# REV_SPARC_CNC_with_battery.net
KiCad netlist of a schematic drawn in EAGLE
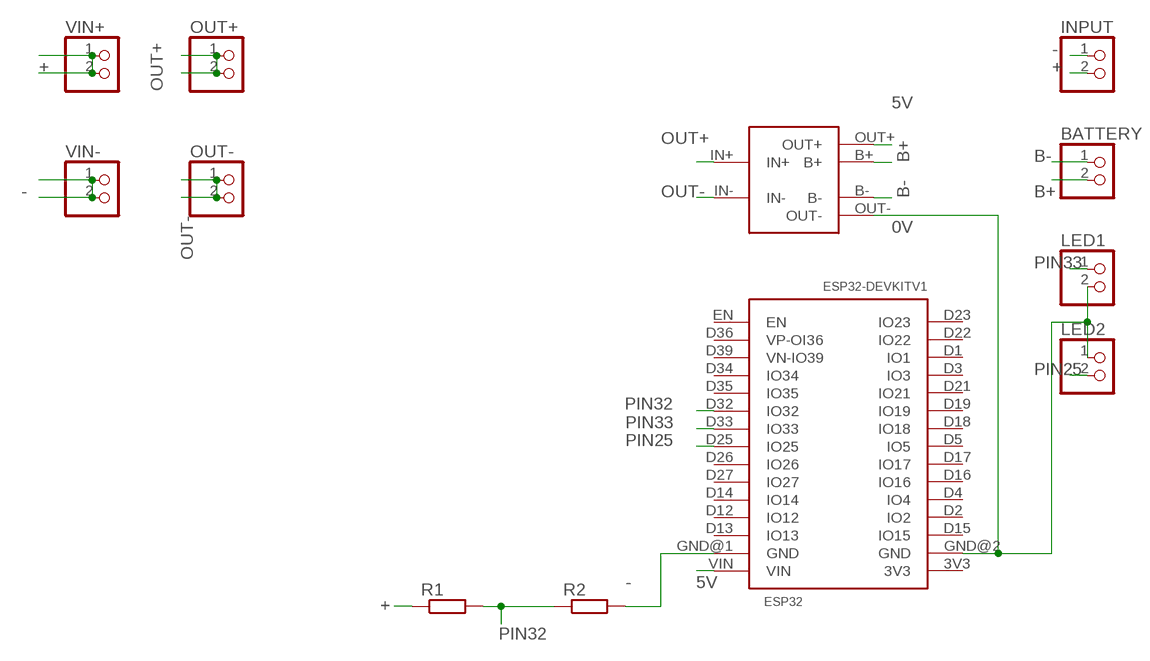
[diagram p0: schematic, sheet 1]

(export (version "E")
  (design (tool "Eeschema 10.0.6"))
  (components
    (comp (ref "BATTERY")
      (value "PINHD-1X02_2.54")
      (footprint "eagle-import:1X02")
      (libsource (lib "eagle-import") (part "PINHD-1X02_2.54"))
    )
    (comp (ref "ESP32")
      (value "ESP32DEVKITV1")
      (footprint "eagle-import:ESP32-DEVKITV1")
      (libsource (lib "eagle-import") (part "ESP32DEVKITV1"))
    )
    (comp (ref "INPUT")
      (value "PINHD-1X2")
      (footprint "eagle-import:1X02")
      (libsource (lib "eagle-import") (part "PINHD-1X2"))
    )
    (comp (ref "LED1")
      (value "PINHD-1X2")
      (footprint "eagle-import:1X02")
      (libsource (lib "eagle-import") (part "PINHD-1X2"))
    )
    (comp (ref "LED2")
      (value "PINHD-1X2")
      (footprint "eagle-import:1X02")
      (libsource (lib "eagle-import") (part "PINHD-1X2"))
    )
    (comp (ref "OUT+")
      (value "PINHD-1X2")
      (footprint "eagle-import:1X02")
      (libsource (lib "eagle-import") (part "PINHD-1X2"))
    )
    (comp (ref "OUT-")
      (value "PINHD-1X2")
      (footprint "eagle-import:1X02")
      (libsource (lib "eagle-import") (part "PINHD-1X2"))
    )
    (comp (ref "R1")
      (value "R-EU_0207/10")
      (footprint "eagle-import:0207_10")
      (libsource (lib "eagle-import") (part "R-EU_0207/10"))
    )
    (comp (ref "R2")
      (value "R-EU_0207/10")
      (footprint "eagle-import:0207_10")
      (libsource (lib "eagle-import") (part "R-EU_0207/10"))
    )
    (comp (ref "TP")
      (value "TP4056-PTH")
      (footprint "eagle-import:TP4056-PTH")
      (libsource (lib "eagle-import") (part "TP4056-PTH"))
    )
    (comp (ref "VIN+")
      (value "PINHD-1X2")
      (footprint "eagle-import:1X02")
      (libsource (lib "eagle-import") (part "PINHD-1X2"))
    )
    (comp (ref "VIN-")
      (value "PINHD-1X2")
      (footprint "eagle-import:1X02")
      (libsource (lib "eagle-import") (part "PINHD-1X2"))
    )
  )
  (nets
    (net (code "1") (name "/+") (class "Default")
      (node (ref "INPUT") (pin "2") (pinfunction "2_2") (pintype "passive"))
      (node (ref "R1") (pin "1") (pinfunction "1_1") (pintype "passive"))
      (node (ref "VIN+") (pin "1") (pinfunction "1_1") (pintype "passive"))
      (node (ref "VIN+") (pin "2") (pinfunction "2_2") (pintype "passive"))
    )
    (net (code "2") (name "/-") (class "Default")
      (node (ref "ESP32") (pin "GND@1") (pinfunction "GND_GND@1") (pintype "bidirectional"))
      (node (ref "INPUT") (pin "1") (pinfunction "1_1") (pintype "passive"))
      (node (ref "R2") (pin "2") (pinfunction "2_2") (pintype "passive"))
      (node (ref "VIN-") (pin "1") (pinfunction "1_1") (pintype "passive"))
      (node (ref "VIN-") (pin "2") (pinfunction "2_2") (pintype "passive"))
    )
    (net (code "3") (name "/0V") (class "Default")
      (node (ref "ESP32") (pin "GND@2") (pinfunction "GND_GND@2") (pintype "bidirectional"))
      (node (ref "LED1") (pin "2") (pinfunction "2_2") (pintype "passive"))
      (node (ref "LED2") (pin "1") (pinfunction "1_1") (pintype "passive"))
      (node (ref "TP") (pin "OUT-") (pinfunction "OUT-_OUT-") (pintype "bidirectional"))
    )
    (net (code "4") (name "/5V") (class "Default")
      (node (ref "ESP32") (pin "VIN") (pinfunction "VIN_VIN") (pintype "bidirectional"))
      (node (ref "TP") (pin "OUT+") (pinfunction "OUT+_OUT+") (pintype "bidirectional"))
    )
    (net (code "5") (name "/B+") (class "Default")
      (node (ref "BATTERY") (pin "2") (pinfunction "2_2") (pintype "passive"))
      (node (ref "TP") (pin "B+") (pinfunction "B+_B+") (pintype "bidirectional"))
    )
    (net (code "6") (name "/B-") (class "Default")
      (node (ref "BATTERY") (pin "1") (pinfunction "1_1") (pintype "passive"))
      (node (ref "TP") (pin "B-") (pinfunction "B-_B-") (pintype "bidirectional"))
    )
    (net (code "7") (name "/OUT+") (class "Default")
      (node (ref "OUT+") (pin "1") (pinfunction "1_1") (pintype "passive"))
      (node (ref "OUT+") (pin "2") (pinfunction "2_2") (pintype "passive"))
      (node (ref "TP") (pin "IN+") (pinfunction "IN+_IN+") (pintype "bidirectional"))
    )
    (net (code "8") (name "/OUT-") (class "Default")
      (node (ref "OUT-") (pin "1") (pinfunction "1_1") (pintype "passive"))
      (node (ref "OUT-") (pin "2") (pinfunction "2_2") (pintype "passive"))
      (node (ref "TP") (pin "IN-") (pinfunction "IN-_IN-") (pintype "bidirectional"))
    )
    (net (code "9") (name "/PIN25") (class "Default")
      (node (ref "ESP32") (pin "D25") (pinfunction "IO25_D25") (pintype "bidirectional"))
      (node (ref "LED2") (pin "2") (pinfunction "2_2") (pintype "passive"))
    )
    (net (code "10") (name "/PIN32") (class "Default")
      (node (ref "ESP32") (pin "D32") (pinfunction "IO32_D32") (pintype "bidirectional"))
      (node (ref "R1") (pin "2") (pinfunction "2_2") (pintype "passive"))
      (node (ref "R2") (pin "1") (pinfunction "1_1") (pintype "passive"))
    )
    (net (code "11") (name "/PIN33") (class "Default")
      (node (ref "ESP32") (pin "D33") (pinfunction "IO33_D33") (pintype "bidirectional"))
      (node (ref "LED1") (pin "1") (pinfunction "1_1") (pintype "passive"))
    )
    (net (code "12") (name "unconnected-(ESP32-IO1-PadD1)") (class "Default")
      (node (ref "ESP32") (pin "D1") (pinfunction "IO1_D1") (pintype "bidirectional"))
    )
    (net (code "13") (name "unconnected-(ESP32-IO2-PadD2)") (class "Default")
      (node (ref "ESP32") (pin "D2") (pinfunction "IO2_D2") (pintype "bidirectional"))
    )
    (net (code "14") (name "unconnected-(ESP32-IO3-PadD3)") (class "Default")
      (node (ref "ESP32") (pin "D3") (pinfunction "IO3_D3") (pintype "bidirectional"))
    )
    (net (code "15") (name "unconnected-(ESP32-IO4-PadD4)") (class "Default")
      (node (ref "ESP32") (pin "D4") (pinfunction "IO4_D4") (pintype "bidirectional"))
    )
    (net (code "16") (name "unconnected-(ESP32-IO5-PadD5)") (class "Default")
      (node (ref "ESP32") (pin "D5") (pinfunction "IO5_D5") (pintype "bidirectional"))
    )
    (net (code "17") (name "unconnected-(ESP32-IO12-PadD12)") (class "Default")
      (node (ref "ESP32") (pin "D12") (pinfunction "IO12_D12") (pintype "bidirectional"))
    )
    (net (code "18") (name "unconnected-(ESP32-IO13-PadD13)") (class "Default")
      (node (ref "ESP32") (pin "D13") (pinfunction "IO13_D13") (pintype "bidirectional"))
    )
    (net (code "19") (name "unconnected-(ESP32-IO14-PadD14)") (class "Default")
      (node (ref "ESP32") (pin "D14") (pinfunction "IO14_D14") (pintype "bidirectional"))
    )
    (net (code "20") (name "unconnected-(ESP32-IO15-PadD15)") (class "Default")
      (node (ref "ESP32") (pin "D15") (pinfunction "IO15_D15") (pintype "bidirectional"))
    )
    (net (code "21") (name "unconnected-(ESP32-IO16-PadD16)") (class "Default")
      (node (ref "ESP32") (pin "D16") (pinfunction "IO16_D16") (pintype "bidirectional"))
    )
    (net (code "22") (name "unconnected-(ESP32-IO17-PadD17)") (class "Default")
      (node (ref "ESP32") (pin "D17") (pinfunction "IO17_D17") (pintype "bidirectional"))
    )
    (net (code "23") (name "unconnected-(ESP32-IO18-PadD18)") (class "Default")
      (node (ref "ESP32") (pin "D18") (pinfunction "IO18_D18") (pintype "bidirectional"))
    )
    (net (code "24") (name "unconnected-(ESP32-IO19-PadD19)") (class "Default")
      (node (ref "ESP32") (pin "D19") (pinfunction "IO19_D19") (pintype "bidirectional"))
    )
    (net (code "25") (name "unconnected-(ESP32-IO21-PadD21)") (class "Default")
      (node (ref "ESP32") (pin "D21") (pinfunction "IO21_D21") (pintype "bidirectional"))
    )
    (net (code "26") (name "unconnected-(ESP32-IO22-PadD22)") (class "Default")
      (node (ref "ESP32") (pin "D22") (pinfunction "IO22_D22") (pintype "bidirectional"))
    )
    (net (code "27") (name "unconnected-(ESP32-IO23-PadD23)") (class "Default")
      (node (ref "ESP32") (pin "D23") (pinfunction "IO23_D23") (pintype "bidirectional"))
    )
    (net (code "28") (name "unconnected-(ESP32-IO26-PadD26)") (class "Default")
      (node (ref "ESP32") (pin "D26") (pinfunction "IO26_D26") (pintype "bidirectional"))
    )
    (net (code "29") (name "unconnected-(ESP32-IO27-PadD27)") (class "Default")
      (node (ref "ESP32") (pin "D27") (pinfunction "IO27_D27") (pintype "bidirectional"))
    )
    (net (code "30") (name "unconnected-(ESP32-IO34-PadD34)") (class "Default")
      (node (ref "ESP32") (pin "D34") (pinfunction "IO34_D34") (pintype "bidirectional"))
    )
    (net (code "31") (name "unconnected-(ESP32-IO35-PadD35)") (class "Default")
      (node (ref "ESP32") (pin "D35") (pinfunction "IO35_D35") (pintype "bidirectional"))
    )
    (net (code "32") (name "unconnected-(ESP32-Pad3V3)") (class "Default")
      (node (ref "ESP32") (pin "3V3") (pinfunction "3V3_3V3") (pintype "bidirectional"))
    )
    (net (code "33") (name "unconnected-(ESP32-PadEN)") (class "Default")
      (node (ref "ESP32") (pin "EN") (pinfunction "EN_EN") (pintype "bidirectional"))
    )
    (net (code "34") (name "unconnected-(ESP32-VN-IO39-PadD39)") (class "Default")
      (node (ref "ESP32") (pin "D39") (pinfunction "VN-IO39_D39") (pintype "bidirectional"))
    )
    (net (code "35") (name "unconnected-(ESP32-VP-OI36-PadD36)") (class "Default")
      (node (ref "ESP32") (pin "D36") (pinfunction "VP-OI36_D36") (pintype "bidirectional"))
    )
  )
)
